# Ethernet_Jack.net
KiCad netlist of a schematic drawn in Altium Designer
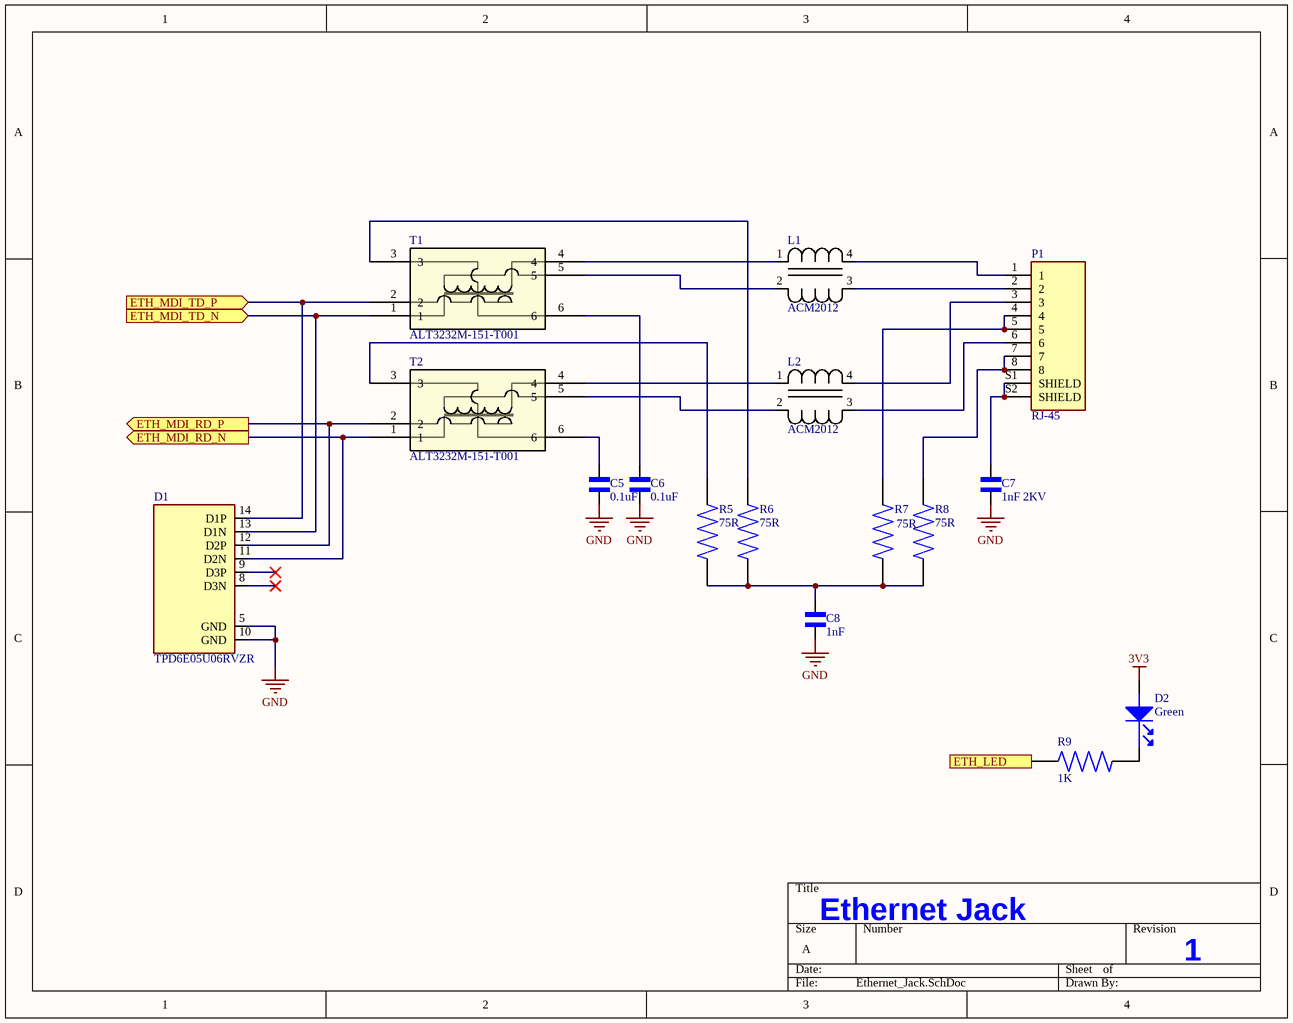
[diagram p0: Ethernet_Jack.SchDoc]

(export (version "E")
  (design (tool "Eeschema 10.0.6"))
  (components
    (comp (ref "C5")
      (value "0.1uF")
      (footprint "C0402")
      (description "CAP CER 0.1UF 6.3V X5R 01005")
      (fields
        (field (name "MANUFACTURER") "Murata")
        (field (name "MANUFACTURER PART NUMBER") "GRM022R60J104KE15L")
      )
      (libsource (lib "nnts") (part "GRM022R60J104KE15L"))
    )
    (comp (ref "C6")
      (value "0.1uF")
      (footprint "C0402")
      (description "CAP CER 0.1UF 6.3V X5R 01005")
      (fields
        (field (name "MANUFACTURER") "Murata")
        (field (name "MANUFACTURER PART NUMBER") "GRM022R60J104KE15L")
      )
      (libsource (lib "nnts") (part "GRM022R60J104KE15L"))
    )
    (comp (ref "C7")
      (value "1nF 2KV")
      (footprint "RESC1206X70N")
      (description "1206 1000 pF 2000 V ±10 % Tolerance X7R SMT Multilayer Ceramic Capacitor")
      (fields
        (field (name "MANUFACTURER") "Kyocera AVX")
        (field (name "MANUFACTURER PART NUMBER") "1206GC102KAT3A")
      )
      (libsource (lib "nnts") (part "1206GC102KAT3A"))
    )
    (comp (ref "C8")
      (value "1nF")
      (footprint "C0402")
      (description "0402 1 nF 6.3 V ±10% Tolerance X5R SMT Multilayer Ceramic Capacitor")
      (fields
        (field (name "MANUFACTURER") "Murata")
        (field (name "MANUFACTURER PART NUMBER") "GRM155R60J102KA01D")
      )
      (libsource (lib "nnts") (part "GRM155R60J102KA01D"))
    )
    (comp (ref "D1")
      (value "TPD6E05U06RVZR")
      (footprint "SON50P135X350X55-14N")
      (description "TVS DIODE 5.5V 14V 14USON (ESD Protection for PHY)")
      (fields (field (name "MANUFACTURER") "Texas Instruments"))
      (libsource (lib "nnts") (part "TPD6E05U06RVZR"))
    )
    (comp (ref "D2")
      (value "Green")
      (footprint "LED_0603")
      (description "LED Uni-Color Green 572nm 2-Pin Chip 0603(1608Metric) T/R")
      (fields
        (field (name "MANUFACTURER") "Osram Opto")
        (field (name "MANUFACTURER PART NUMBER") "LGL29K-G2J1-24-Z")
      )
      (libsource (lib "nnts") (part "LGL29K-G2J1-24-Z"))
    )
    (comp (ref "L1")
      (value "ACM2012")
      (footprint "IND_TDK_ACM2012_2P_TDK-M")
      (description "TDK - ACM2012-121-2P-T002 - Filter, Common Mode, ACM Series, 120 ohm, 370 mA, 2mm x 1.2mm x 1.3mm")
      (fields
        (field (name "MANUFACTURER") "TDK")
        (field (name "MANUFACTURER PART NUMBER") "ACM2012-121-2P-T002")
      )
      (libsource (lib "nnts") (part "ACM2012-121-2P-T002"))
    )
    (comp (ref "L2")
      (value "ACM2012")
      (footprint "IND_TDK_ACM2012_2P_TDK-M")
      (description "TDK - ACM2012-121-2P-T002 - Filter, Common Mode, ACM Series, 120 ohm, 370 mA, 2mm x 1.2mm x 1.3mm")
      (fields
        (field (name "MANUFACTURER") "TDK")
        (field (name "MANUFACTURER PART NUMBER") "ACM2012-121-2P-T002")
      )
      (libsource (lib "nnts") (part "ACM2012-121-2P-T002"))
    )
    (comp (ref "P1")
      (value "RJ-45")
      (footprint "TE_1-406541-5")
      (description "Conn RJ-45 F 8 POS 2.04mm Solder RA Thru-Hole 8 Terminal 1 Port Tray Cat 5")
      (fields
        (field (name "MANUFACTURER") "TE Connectivity")
        (field (name "MANUFACTURER PART NUMBER") "1-406541-5")
      )
      (libsource (lib "nnts") (part "1-406541-5"))
    )
    (comp (ref "R5")
      (value "75R")
      (footprint "R0402 Vishay")
      (fields
        (field (name "MANUFACTURER") "Vishay")
        (field (name "MANUFACTURER PART NUMBER") "CRCW040275R0FKED")
        (field (name "TOLERANCE") "1%")
      )
      (libsource (lib "nnts") (part "CRCW040275R0FKED"))
    )
    (comp (ref "R6")
      (value "75R")
      (footprint "R0402 Vishay")
      (fields
        (field (name "MANUFACTURER") "Vishay")
        (field (name "MANUFACTURER PART NUMBER") "CRCW040275R0FKED")
        (field (name "TOLERANCE") "1%")
      )
      (libsource (lib "nnts") (part "CRCW040275R0FKED"))
    )
    (comp (ref "R7")
      (value "75R")
      (footprint "R0402 Vishay")
      (fields
        (field (name "MANUFACTURER") "Vishay")
        (field (name "MANUFACTURER PART NUMBER") "CRCW040275R0FKED")
        (field (name "TOLERANCE") "1%")
      )
      (libsource (lib "nnts") (part "CRCW040275R0FKED"))
    )
    (comp (ref "R8")
      (value "75R")
      (footprint "R0402 Vishay")
      (fields
        (field (name "MANUFACTURER") "Vishay")
        (field (name "MANUFACTURER PART NUMBER") "CRCW040275R0FKED")
        (field (name "TOLERANCE") "1%")
      )
      (libsource (lib "nnts") (part "CRCW040275R0FKED"))
    )
    (comp (ref "R9")
      (value "1K")
      (footprint "R0603 Vishay")
      (description "Res Thick Film 0201 1K Ohm 1% 1/20W 200ppm/C Molded SMD SMD Paper T/R")
      (fields
        (field (name "MANUFACTURER") "Vishay")
        (field (name "MANUFACTURER PART NUMBER") "CRCW02011K00FNED")
      )
      (libsource (lib "nnts") (part "CRCW02011K00FNED"))
    )
    (comp (ref "T1")
      (value "ALT3232M-151-T001")
      (footprint "ALT3232M-151-T001")
      (description "t600,601")
      (fields (field (name "COPYRIGHT") "Copyright (C) 2018 Accelerated Designs. All rights reserved"))
      (libsource (lib "nnts") (part "ALT3232M-151-T001"))
    )
    (comp (ref "T2")
      (value "ALT3232M-151-T001")
      (footprint "ALT3232M-151-T001")
      (description "t600,601")
      (fields (field (name "COPYRIGHT") "Copyright (C) 2018 Accelerated Designs. All rights reserved"))
      (libsource (lib "nnts") (part "ALT3232M-151-T001"))
    )
  )
  (nets
    (net (code "1") (name "/ETH_LED") (class "Default")
      (node (ref "R9") (pin "1") (pinfunction "1_1") (pintype "passive"))
    )
    (net (code "2") (name "/ETH_MDI_RD_N") (class "Default")
      (node (ref "D1") (pin "11") (pinfunction "D2N_11") (pintype "bidirectional"))
      (node (ref "T2") (pin "1") (pinfunction "1_1") (pintype "passive"))
    )
    (net (code "3") (name "/ETH_MDI_RD_P") (class "Default")
      (node (ref "D1") (pin "12") (pinfunction "D2P_12") (pintype "bidirectional"))
      (node (ref "T2") (pin "2") (pinfunction "2_2") (pintype "passive"))
    )
    (net (code "4") (name "/ETH_MDI_TD_N") (class "Default")
      (node (ref "D1") (pin "13") (pinfunction "D1N_13") (pintype "bidirectional"))
      (node (ref "T1") (pin "1") (pinfunction "1_1") (pintype "passive"))
    )
    (net (code "5") (name "/ETH_MDI_TD_P") (class "Default")
      (node (ref "D1") (pin "14") (pinfunction "D1P_14") (pintype "bidirectional"))
      (node (ref "T1") (pin "2") (pinfunction "2_2") (pintype "passive"))
    )
    (net (code "6") (name "3V3") (class "Default")
      (node (ref "D2") (pin "1") (pinfunction "Anode_1") (pintype "passive"))
    )
    (net (code "7") (name "GND") (class "Default")
      (node (ref "C5") (pin "1") (pinfunction "1_1") (pintype "passive"))
      (node (ref "C6") (pin "1") (pinfunction "1_1") (pintype "passive"))
      (node (ref "C7") (pin "1") (pinfunction "1_1") (pintype "passive"))
      (node (ref "C8") (pin "1") (pinfunction "1_1") (pintype "passive"))
      (node (ref "D1") (pin "10") (pinfunction "GND_10") (pintype "power_in"))
      (node (ref "D1") (pin "5") (pinfunction "GND_5") (pintype "power_in"))
    )
    (net (code "8") (name "Net-(C5-Pad2)") (class "Default")
      (node (ref "C5") (pin "2") (pinfunction "2_2") (pintype "passive"))
      (node (ref "T2") (pin "6") (pinfunction "6_6") (pintype "passive"))
    )
    (net (code "9") (name "Net-(C6-Pad2)") (class "Default")
      (node (ref "C6") (pin "2") (pinfunction "2_2") (pintype "passive"))
      (node (ref "T1") (pin "6") (pinfunction "6_6") (pintype "passive"))
    )
    (net (code "10") (name "Net-(C7-Pad2)") (class "Default")
      (node (ref "C7") (pin "2") (pinfunction "2_2") (pintype "passive"))
      (node (ref "P1") (pin "S1") (pinfunction "SHIELD_S1") (pintype "passive"))
      (node (ref "P1") (pin "S2") (pinfunction "SHIELD_S2") (pintype "passive"))
    )
    (net (code "11") (name "Net-(C8-Pad2)") (class "Default")
      (node (ref "C8") (pin "2") (pinfunction "2_2") (pintype "passive"))
      (node (ref "R5") (pin "1") (pinfunction "1_1") (pintype "passive"))
      (node (ref "R6") (pin "1") (pinfunction "1_1") (pintype "passive"))
      (node (ref "R7") (pin "1") (pinfunction "1_1") (pintype "passive"))
      (node (ref "R8") (pin "1") (pinfunction "1_1") (pintype "passive"))
    )
    (net (code "12") (name "Net-(D2-Cathode)") (class "Default")
      (node (ref "D2") (pin "2") (pinfunction "Cathode_2") (pintype "passive"))
      (node (ref "R9") (pin "2") (pinfunction "2_2") (pintype "passive"))
    )
    (net (code "13") (name "Net-(L1-Pad1)") (class "Default")
      (node (ref "L1") (pin "1") (pinfunction "1_1") (pintype "passive"))
      (node (ref "T1") (pin "4") (pinfunction "4_4") (pintype "passive"))
    )
    (net (code "14") (name "Net-(L1-Pad2)") (class "Default")
      (node (ref "L1") (pin "2") (pinfunction "2_2") (pintype "passive"))
      (node (ref "T1") (pin "5") (pinfunction "5_5") (pintype "passive"))
    )
    (net (code "15") (name "Net-(L1-Pad3)") (class "Default")
      (node (ref "L1") (pin "3") (pinfunction "3_3") (pintype "passive"))
      (node (ref "P1") (pin "2") (pinfunction "2_2") (pintype "passive"))
    )
    (net (code "16") (name "Net-(L1-Pad4)") (class "Default")
      (node (ref "L1") (pin "4") (pinfunction "4_4") (pintype "passive"))
      (node (ref "P1") (pin "1") (pinfunction "1_1") (pintype "passive"))
    )
    (net (code "17") (name "Net-(L2-Pad1)") (class "Default")
      (node (ref "L2") (pin "1") (pinfunction "1_1") (pintype "passive"))
      (node (ref "T2") (pin "4") (pinfunction "4_4") (pintype "passive"))
    )
    (net (code "18") (name "Net-(L2-Pad2)") (class "Default")
      (node (ref "L2") (pin "2") (pinfunction "2_2") (pintype "passive"))
      (node (ref "T2") (pin "5") (pinfunction "5_5") (pintype "passive"))
    )
    (net (code "19") (name "Net-(L2-Pad3)") (class "Default")
      (node (ref "L2") (pin "3") (pinfunction "3_3") (pintype "passive"))
      (node (ref "P1") (pin "6") (pinfunction "6_6") (pintype "passive"))
    )
    (net (code "20") (name "Net-(L2-Pad4)") (class "Default")
      (node (ref "L2") (pin "4") (pinfunction "4_4") (pintype "passive"))
      (node (ref "P1") (pin "3") (pinfunction "3_3") (pintype "passive"))
    )
    (net (code "21") (name "Net-(P1-Pad4)") (class "Default")
      (node (ref "P1") (pin "4") (pinfunction "4_4") (pintype "passive"))
      (node (ref "P1") (pin "5") (pinfunction "5_5") (pintype "passive"))
      (node (ref "R7") (pin "2") (pinfunction "2_2") (pintype "passive"))
    )
    (net (code "22") (name "Net-(P1-Pad7)") (class "Default")
      (node (ref "P1") (pin "7") (pinfunction "7_7") (pintype "passive"))
      (node (ref "P1") (pin "8") (pinfunction "8_8") (pintype "passive"))
      (node (ref "R8") (pin "2") (pinfunction "2_2") (pintype "passive"))
    )
    (net (code "23") (name "Net-(R5-Pad2)") (class "Default")
      (node (ref "R5") (pin "2") (pinfunction "2_2") (pintype "passive"))
      (node (ref "T2") (pin "3") (pinfunction "3_3") (pintype "passive"))
    )
    (net (code "24") (name "Net-(R6-Pad2)") (class "Default")
      (node (ref "R6") (pin "2") (pinfunction "2_2") (pintype "passive"))
      (node (ref "T1") (pin "3") (pinfunction "3_3") (pintype "passive"))
    )
    (net (code "25") (name "unconnected-(D1-D3N-Pad8)") (class "Default")
      (node (ref "D1") (pin "8") (pinfunction "D3N_8") (pintype "bidirectional+no_connect"))
    )
    (net (code "26") (name "unconnected-(D1-D3P-Pad9)") (class "Default")
      (node (ref "D1") (pin "9") (pinfunction "D3P_9") (pintype "bidirectional+no_connect"))
    )
  )
)
